# powerboard.net
KiCad netlist of a schematic drawn in EAGLE
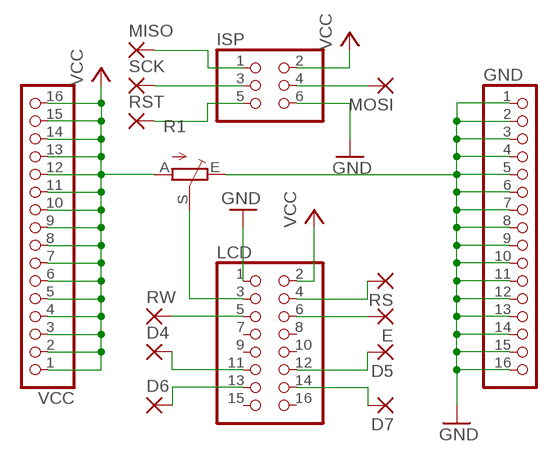
[diagram p0: schematic, sheet 1]

(export (version "E")
  (design (tool "Eeschema 10.0.6"))
  (components
    (comp (ref "D4")
      (value "2,54/1,1")
      (footprint "eagle-import:2,54_1,1")
      (libsource (lib "eagle-import") (part "2,54/1,1"))
    )
    (comp (ref "D5")
      (value "2,54/1,1")
      (footprint "eagle-import:2,54_1,1")
      (libsource (lib "eagle-import") (part "2,54/1,1"))
    )
    (comp (ref "D6")
      (value "2,54/1,1")
      (footprint "eagle-import:2,54_1,1")
      (libsource (lib "eagle-import") (part "2,54/1,1"))
    )
    (comp (ref "D7")
      (value "2,54/1,1")
      (footprint "eagle-import:2,54_1,1")
      (libsource (lib "eagle-import") (part "2,54/1,1"))
    )
    (comp (ref "E")
      (value "2,54/1,1")
      (footprint "eagle-import:2,54_1,1")
      (libsource (lib "eagle-import") (part "2,54/1,1"))
    )
    (comp (ref "GND")
      (value "PINHD-1X16")
      (footprint "eagle-import:1X16")
      (libsource (lib "eagle-import") (part "PINHD-1X16"))
    )
    (comp (ref "ISP")
      (value "PINHD-2X3")
      (footprint "eagle-import:2X03")
      (libsource (lib "eagle-import") (part "PINHD-2X3"))
    )
    (comp (ref "LCD")
      (value "PINHD-2X8")
      (footprint "eagle-import:2X08")
      (libsource (lib "eagle-import") (part "PINHD-2X8"))
    )
    (comp (ref "MISO")
      (value "2,54/1,1")
      (footprint "eagle-import:2,54_1,1")
      (libsource (lib "eagle-import") (part "2,54/1,1"))
    )
    (comp (ref "MOSI")
      (value "2,54/1,1")
      (footprint "eagle-import:2,54_1,1")
      (libsource (lib "eagle-import") (part "2,54/1,1"))
    )
    (comp (ref "R1")
      (value "TRIM_EU-LI10")
      (footprint "eagle-import:LI10")
      (libsource (lib "eagle-import") (part "TRIM_EU-LI10"))
    )
    (comp (ref "RS")
      (value "2,54/1,1")
      (footprint "eagle-import:2,54_1,1")
      (libsource (lib "eagle-import") (part "2,54/1,1"))
    )
    (comp (ref "RST")
      (value "2,54/1,1")
      (footprint "eagle-import:2,54_1,1")
      (libsource (lib "eagle-import") (part "2,54/1,1"))
    )
    (comp (ref "RW")
      (value "2,54/1,1")
      (footprint "eagle-import:2,54_1,1")
      (libsource (lib "eagle-import") (part "2,54/1,1"))
    )
    (comp (ref "SCK")
      (value "2,54/1,1")
      (footprint "eagle-import:2,54_1,1")
      (libsource (lib "eagle-import") (part "2,54/1,1"))
    )
    (comp (ref "VCC")
      (value "PINHD-1X16")
      (footprint "eagle-import:1X16")
      (libsource (lib "eagle-import") (part "PINHD-1X16"))
    )
  )
  (nets
    (net (code "1") (name "GND") (class "Default")
      (node (ref "GND") (pin "1") (pinfunction "1_1") (pintype "passive"))
      (node (ref "GND") (pin "10") (pinfunction "10_10") (pintype "passive"))
      (node (ref "GND") (pin "11") (pinfunction "11_11") (pintype "passive"))
      (node (ref "GND") (pin "12") (pinfunction "12_12") (pintype "passive"))
      (node (ref "GND") (pin "13") (pinfunction "13_13") (pintype "passive"))
      (node (ref "GND") (pin "14") (pinfunction "14_14") (pintype "passive"))
      (node (ref "GND") (pin "15") (pinfunction "15_15") (pintype "passive"))
      (node (ref "GND") (pin "16") (pinfunction "16_16") (pintype "passive"))
      (node (ref "GND") (pin "2") (pinfunction "2_2") (pintype "passive"))
      (node (ref "GND") (pin "3") (pinfunction "3_3") (pintype "passive"))
      (node (ref "GND") (pin "4") (pinfunction "4_4") (pintype "passive"))
      (node (ref "GND") (pin "5") (pinfunction "5_5") (pintype "passive"))
      (node (ref "GND") (pin "6") (pinfunction "6_6") (pintype "passive"))
      (node (ref "GND") (pin "7") (pinfunction "7_7") (pintype "passive"))
      (node (ref "GND") (pin "8") (pinfunction "8_8") (pintype "passive"))
      (node (ref "GND") (pin "9") (pinfunction "9_9") (pintype "passive"))
      (node (ref "ISP") (pin "6") (pinfunction "6_6") (pintype "passive"))
      (node (ref "LCD") (pin "1") (pinfunction "1_1") (pintype "passive"))
      (node (ref "R1") (pin "E") (pinfunction "E_E") (pintype "passive"))
    )
    (net (code "2") (name "Net-(D4-P)") (class "Default")
      (node (ref "D4") (pin "1") (pinfunction "P_1") (pintype "passive"))
      (node (ref "LCD") (pin "11") (pinfunction "11_11") (pintype "passive"))
    )
    (net (code "3") (name "Net-(D5-P)") (class "Default")
      (node (ref "D5") (pin "1") (pinfunction "P_1") (pintype "passive"))
      (node (ref "LCD") (pin "12") (pinfunction "12_12") (pintype "passive"))
    )
    (net (code "4") (name "Net-(D6-P)") (class "Default")
      (node (ref "D6") (pin "1") (pinfunction "P_1") (pintype "passive"))
      (node (ref "LCD") (pin "13") (pinfunction "13_13") (pintype "passive"))
    )
    (net (code "5") (name "Net-(D7-P)") (class "Default")
      (node (ref "D7") (pin "1") (pinfunction "P_1") (pintype "passive"))
      (node (ref "LCD") (pin "14") (pinfunction "14_14") (pintype "passive"))
    )
    (net (code "6") (name "Net-(E-P)") (class "Default")
      (node (ref "E") (pin "1") (pinfunction "P_1") (pintype "passive"))
      (node (ref "LCD") (pin "6") (pinfunction "6_6") (pintype "passive"))
    )
    (net (code "7") (name "Net-(LCD-Pad3)") (class "Default")
      (node (ref "LCD") (pin "3") (pinfunction "3_3") (pintype "passive"))
      (node (ref "R1") (pin "S") (pinfunction "S_S") (pintype "passive"))
    )
    (net (code "8") (name "Net-(MISO-P)") (class "Default")
      (node (ref "ISP") (pin "1") (pinfunction "1_1") (pintype "passive"))
      (node (ref "MISO") (pin "1") (pinfunction "P_1") (pintype "passive"))
    )
    (net (code "9") (name "Net-(MOSI-P)") (class "Default")
      (node (ref "ISP") (pin "4") (pinfunction "4_4") (pintype "passive"))
      (node (ref "MOSI") (pin "1") (pinfunction "P_1") (pintype "passive"))
    )
    (net (code "10") (name "Net-(RS-P)") (class "Default")
      (node (ref "LCD") (pin "4") (pinfunction "4_4") (pintype "passive"))
      (node (ref "RS") (pin "1") (pinfunction "P_1") (pintype "passive"))
    )
    (net (code "11") (name "Net-(RST-P)") (class "Default")
      (node (ref "ISP") (pin "5") (pinfunction "5_5") (pintype "passive"))
      (node (ref "RST") (pin "1") (pinfunction "P_1") (pintype "passive"))
    )
    (net (code "12") (name "Net-(RW-P)") (class "Default")
      (node (ref "LCD") (pin "5") (pinfunction "5_5") (pintype "passive"))
      (node (ref "RW") (pin "1") (pinfunction "P_1") (pintype "passive"))
    )
    (net (code "13") (name "Net-(SCK-P)") (class "Default")
      (node (ref "ISP") (pin "3") (pinfunction "3_3") (pintype "passive"))
      (node (ref "SCK") (pin "1") (pinfunction "P_1") (pintype "passive"))
    )
    (net (code "14") (name "VCC") (class "Default")
      (node (ref "ISP") (pin "2") (pinfunction "2_2") (pintype "passive"))
      (node (ref "LCD") (pin "2") (pinfunction "2_2") (pintype "passive"))
      (node (ref "R1") (pin "A") (pinfunction "A_A") (pintype "passive"))
      (node (ref "VCC") (pin "1") (pinfunction "1_1") (pintype "passive"))
      (node (ref "VCC") (pin "10") (pinfunction "10_10") (pintype "passive"))
      (node (ref "VCC") (pin "11") (pinfunction "11_11") (pintype "passive"))
      (node (ref "VCC") (pin "12") (pinfunction "12_12") (pintype "passive"))
      (node (ref "VCC") (pin "13") (pinfunction "13_13") (pintype "passive"))
      (node (ref "VCC") (pin "14") (pinfunction "14_14") (pintype "passive"))
      (node (ref "VCC") (pin "15") (pinfunction "15_15") (pintype "passive"))
      (node (ref "VCC") (pin "16") (pinfunction "16_16") (pintype "passive"))
      (node (ref "VCC") (pin "2") (pinfunction "2_2") (pintype "passive"))
      (node (ref "VCC") (pin "3") (pinfunction "3_3") (pintype "passive"))
      (node (ref "VCC") (pin "4") (pinfunction "4_4") (pintype "passive"))
      (node (ref "VCC") (pin "5") (pinfunction "5_5") (pintype "passive"))
      (node (ref "VCC") (pin "6") (pinfunction "6_6") (pintype "passive"))
      (node (ref "VCC") (pin "7") (pinfunction "7_7") (pintype "passive"))
      (node (ref "VCC") (pin "8") (pinfunction "8_8") (pintype "passive"))
      (node (ref "VCC") (pin "9") (pinfunction "9_9") (pintype "passive"))
    )
    (net (code "15") (name "unconnected-(LCD-Pad7)") (class "Default")
      (node (ref "LCD") (pin "7") (pinfunction "7_7") (pintype "passive"))
    )
    (net (code "16") (name "unconnected-(LCD-Pad8)") (class "Default")
      (node (ref "LCD") (pin "8") (pinfunction "8_8") (pintype "passive"))
    )
    (net (code "17") (name "unconnected-(LCD-Pad9)") (class "Default")
      (node (ref "LCD") (pin "9") (pinfunction "9_9") (pintype "passive"))
    )
    (net (code "18") (name "unconnected-(LCD-Pad10)") (class "Default")
      (node (ref "LCD") (pin "10") (pinfunction "10_10") (pintype "passive"))
    )
    (net (code "19") (name "unconnected-(LCD-Pad15)") (class "Default")
      (node (ref "LCD") (pin "15") (pinfunction "15_15") (pintype "passive"))
    )
    (net (code "20") (name "unconnected-(LCD-Pad16)") (class "Default")
      (node (ref "LCD") (pin "16") (pinfunction "16_16") (pintype "passive"))
    )
  )
)
